# relay.net
KiCad netlist of a schematic drawn in Altium Designer
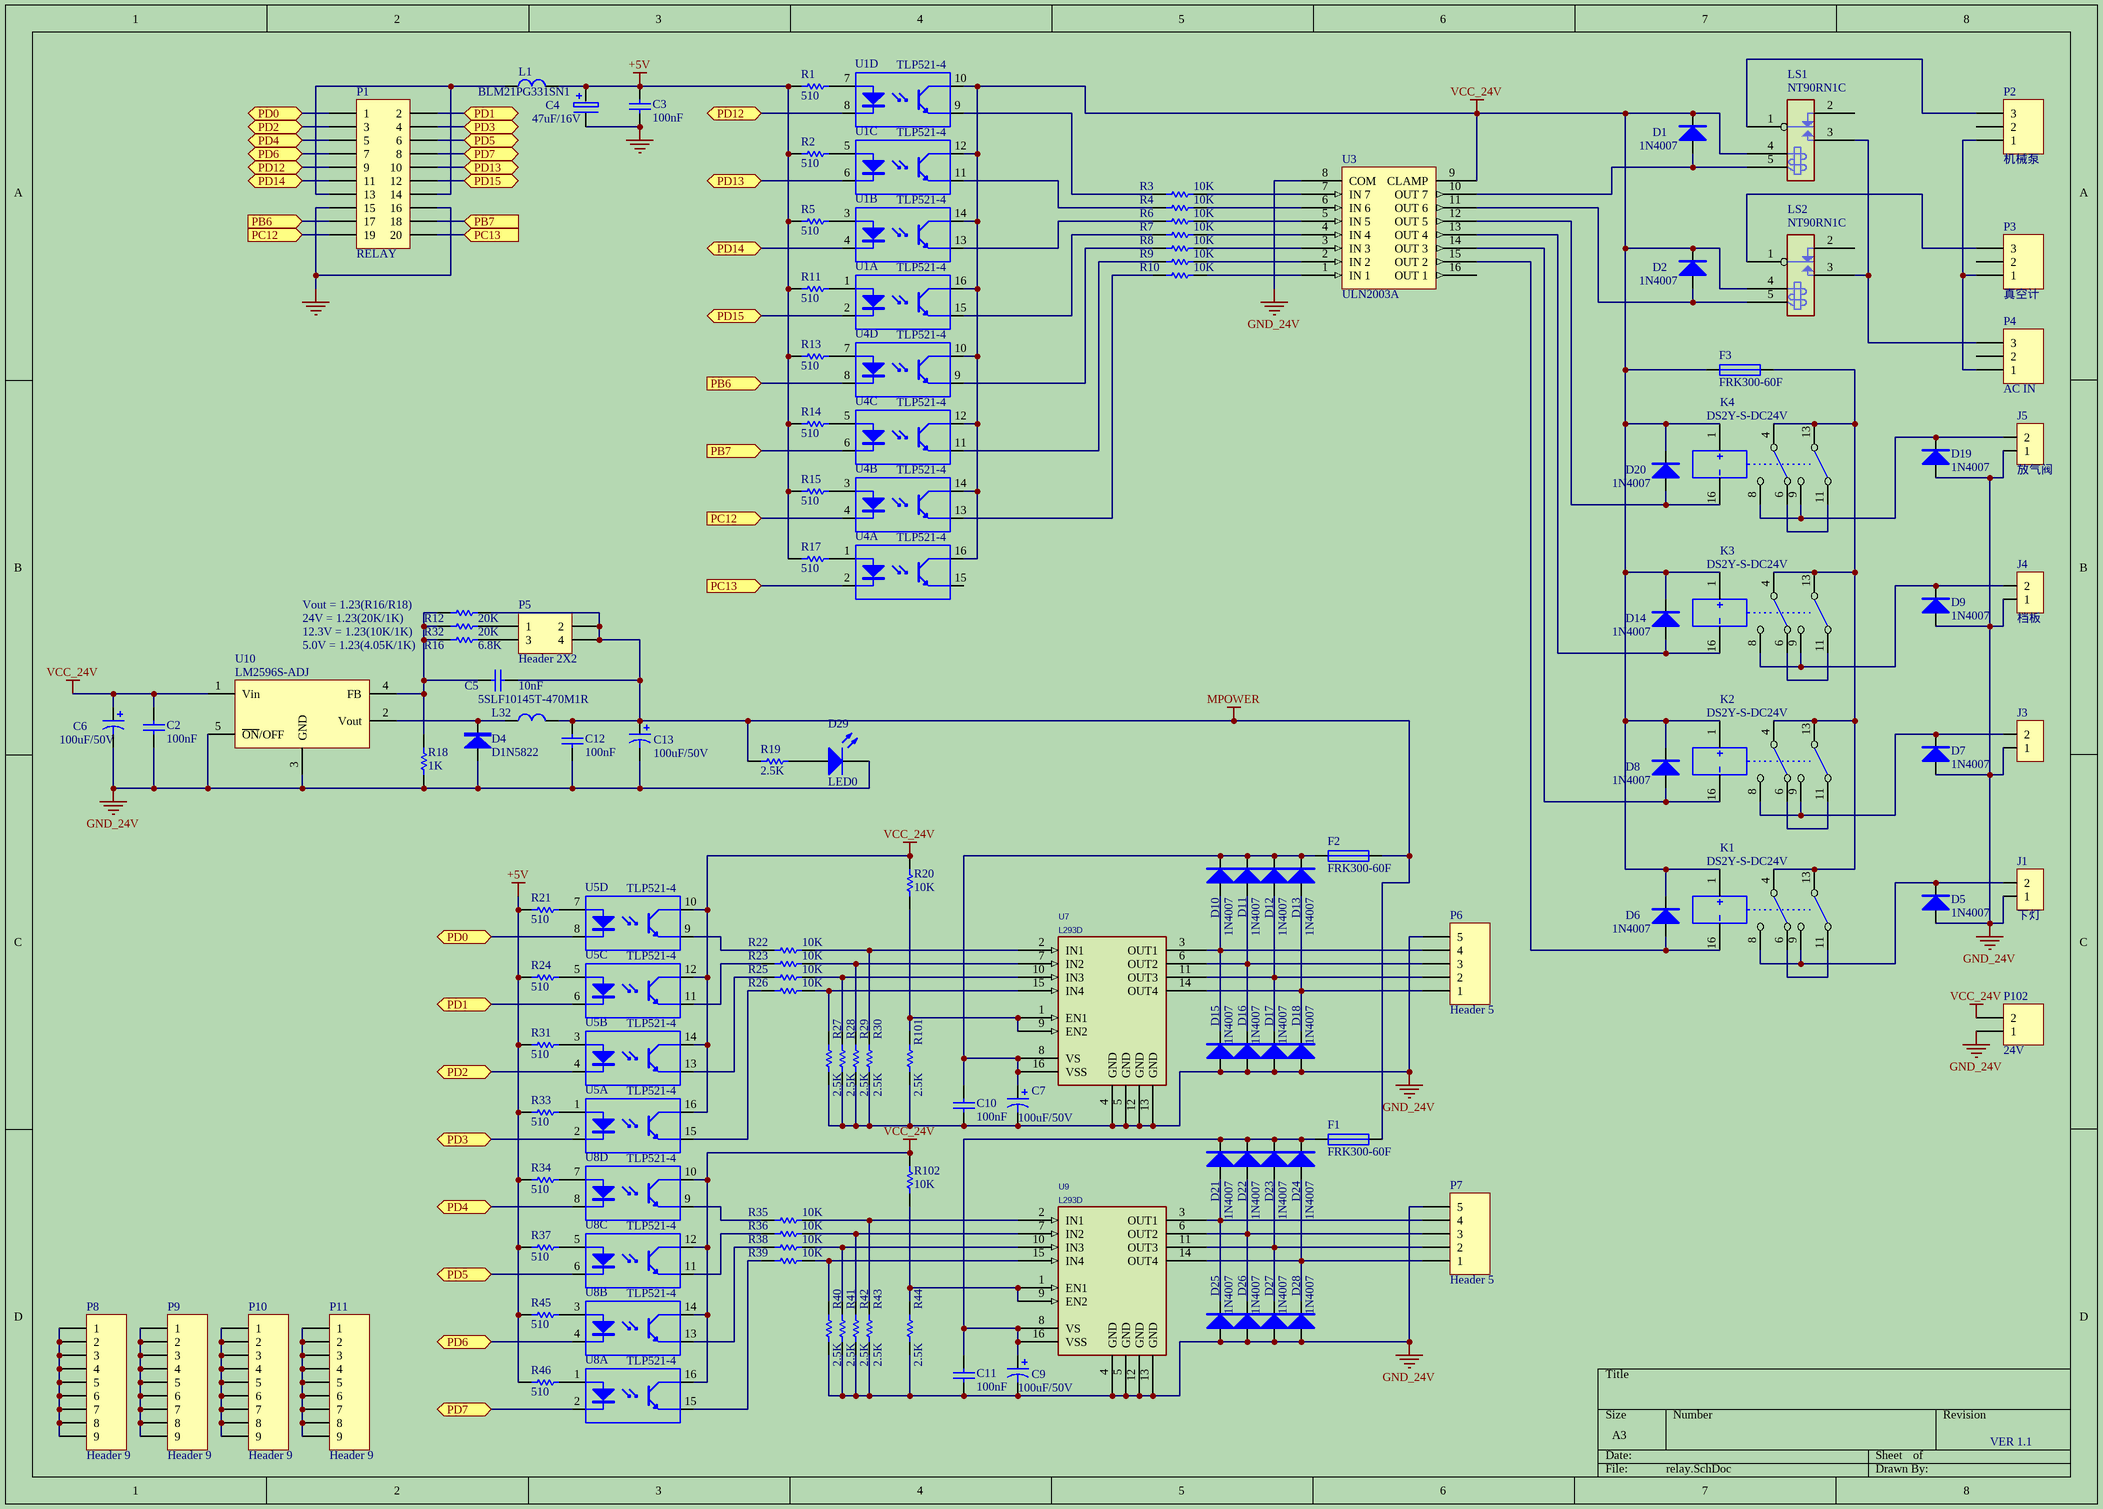
[diagram p0: relay.SchDoc]

(export (version "E")
  (design (tool "Eeschema 10.0.6"))
  (components
    (comp (ref "C2")
      (value "100nF")
      (footprint "C0805")
      (description "Capacitor")
      (fields (field (name "PUBLISHER") "Altium Limited"))
      (libsource (lib "Miscellaneous Devices") (part "Cap"))
    )
    (comp (ref "C3")
      (value "100nF")
      (footprint "贴片元器件:C0805")
      (description "Capacitor")
      (fields (field (name "PUBLISHER") "Altium Limited"))
      (libsource (lib "Miscellaneous Devices") (part "Cap"))
    )
    (comp (ref "C4")
      (value "47uF/16V")
      (footprint "CD1/2")
      (description "Electrolytic Capacitor")
      (libsource (lib "Devices") (part "CD1"))
    )
    (comp (ref "C5")
      (value "10nF")
      (footprint "C0805")
      (description "Capacitor")
      (fields (field (name "PUBLISHER") "Altium Limited"))
      (libsource (lib "Miscellaneous Devices") (part "Cap"))
    )
    (comp (ref "C6")
      (value "100uF/50V")
      (footprint "CD2/4")
      (description "Polarized Capacitor (Radial)")
      (fields (field (name "PUBLISHER") "Altium Limited"))
      (libsource (lib "Miscellaneous Devices") (part "Cap Pol1"))
    )
    (comp (ref "C7")
      (value "100uF/50V")
      (footprint "CD2/4")
      (description "Polarized Capacitor (Radial)")
      (fields (field (name "PUBLISHER") "Altium Limited"))
      (libsource (lib "Miscellaneous Devices") (part "Cap Pol1"))
    )
    (comp (ref "C9")
      (value "100uF/50V")
      (footprint "CD2/4")
      (description "Polarized Capacitor (Radial)")
      (fields (field (name "PUBLISHER") "Altium Limited"))
      (libsource (lib "Miscellaneous Devices") (part "Cap Pol1"))
    )
    (comp (ref "C10")
      (value "100nF")
      (footprint "贴片元器件:C0805")
      (description "Capacitor")
      (fields (field (name "PUBLISHER") "Altium Limited"))
      (libsource (lib "Miscellaneous Devices") (part "Cap"))
    )
    (comp (ref "C11")
      (value "100nF")
      (footprint "贴片元器件:C0805")
      (description "Capacitor")
      (fields (field (name "PUBLISHER") "Altium Limited"))
      (libsource (lib "Miscellaneous Devices") (part "Cap"))
    )
    (comp (ref "C12")
      (value "100nF")
      (footprint "C0805")
      (description "Capacitor")
      (fields (field (name "PUBLISHER") "Altium Limited"))
      (libsource (lib "Miscellaneous Devices") (part "Cap"))
    )
    (comp (ref "C13")
      (value "100uF/50V")
      (footprint "CD2/4")
      (description "Polarized Capacitor (Radial)")
      (fields (field (name "PUBLISHER") "Altium Limited"))
      (libsource (lib "Miscellaneous Devices") (part "Cap Pol1"))
    )
    (comp (ref "D1")
      (value "1N4007")
      (footprint "V3")
      (description "Diode")
      (libsource (lib "Devices") (part "2JG"))
    )
    (comp (ref "D2")
      (value "1N4007")
      (footprint "V3")
      (description "Diode")
      (libsource (lib "Devices") (part "2JG"))
    )
    (comp (ref "D4")
      (value "D1N5822")
      (footprint "DO-201AD-H")
      (description "Diode")
      (libsource (lib "*") (part "DIODE"))
    )
    (comp (ref "D5")
      (value "1N4007")
      (footprint "V3")
      (description "Diode")
      (libsource (lib "Devices") (part "2JG"))
    )
    (comp (ref "D6")
      (value "1N4007")
      (footprint "V3")
      (description "Diode")
      (libsource (lib "Devices") (part "2JG"))
    )
    (comp (ref "D7")
      (value "1N4007")
      (footprint "V3")
      (description "Diode")
      (libsource (lib "Devices") (part "2JG"))
    )
    (comp (ref "D8")
      (value "1N4007")
      (footprint "V3")
      (description "Diode")
      (libsource (lib "Devices") (part "2JG"))
    )
    (comp (ref "D9")
      (value "1N4007")
      (footprint "V3")
      (description "Diode")
      (libsource (lib "Devices") (part "2JG"))
    )
    (comp (ref "D10")
      (value "1N4007")
      (footprint "V3")
      (description "Diode")
      (libsource (lib "Devices") (part "2JG"))
    )
    (comp (ref "D11")
      (value "1N4007")
      (footprint "V3")
      (description "Diode")
      (libsource (lib "Devices") (part "2JG"))
    )
    (comp (ref "D12")
      (value "1N4007")
      (footprint "V3")
      (description "Diode")
      (libsource (lib "Devices") (part "2JG"))
    )
    (comp (ref "D13")
      (value "1N4007")
      (footprint "V3")
      (description "Diode")
      (libsource (lib "Devices") (part "2JG"))
    )
    (comp (ref "D14")
      (value "1N4007")
      (footprint "V3")
      (description "Diode")
      (libsource (lib "Devices") (part "2JG"))
    )
    (comp (ref "D15")
      (value "1N4007")
      (footprint "V3")
      (description "Diode")
      (libsource (lib "Devices") (part "2JG"))
    )
    (comp (ref "D16")
      (value "1N4007")
      (footprint "V3")
      (description "Diode")
      (libsource (lib "Devices") (part "2JG"))
    )
    (comp (ref "D17")
      (value "1N4007")
      (footprint "V3")
      (description "Diode")
      (libsource (lib "Devices") (part "2JG"))
    )
    (comp (ref "D18")
      (value "1N4007")
      (footprint "V3")
      (description "Diode")
      (libsource (lib "Devices") (part "2JG"))
    )
    (comp (ref "D19")
      (value "1N4007")
      (footprint "V3")
      (description "Diode")
      (libsource (lib "Devices") (part "2JG"))
    )
    (comp (ref "D20")
      (value "1N4007")
      (footprint "V3")
      (description "Diode")
      (libsource (lib "Devices") (part "2JG"))
    )
    (comp (ref "D21")
      (value "1N4007")
      (footprint "V3")
      (description "Diode")
      (libsource (lib "Devices") (part "2JG"))
    )
    (comp (ref "D22")
      (value "1N4007")
      (footprint "V3")
      (description "Diode")
      (libsource (lib "Devices") (part "2JG"))
    )
    (comp (ref "D23")
      (value "1N4007")
      (footprint "V3")
      (description "Diode")
      (libsource (lib "Devices") (part "2JG"))
    )
    (comp (ref "D24")
      (value "1N4007")
      (footprint "V3")
      (description "Diode")
      (libsource (lib "Devices") (part "2JG"))
    )
    (comp (ref "D25")
      (value "1N4007")
      (footprint "V3")
      (description "Diode")
      (libsource (lib "Devices") (part "2JG"))
    )
    (comp (ref "D26")
      (value "1N4007")
      (footprint "V3")
      (description "Diode")
      (libsource (lib "Devices") (part "2JG"))
    )
    (comp (ref "D27")
      (value "1N4007")
      (footprint "V3")
      (description "Diode")
      (libsource (lib "Devices") (part "2JG"))
    )
    (comp (ref "D28")
      (value "1N4007")
      (footprint "V3")
      (description "Diode")
      (libsource (lib "Devices") (part "2JG"))
    )
    (comp (ref "D29")
      (value "LED0")
      (footprint "LED0805")
      (description "Typical INFRARED GaAs LED")
      (fields (field (name "PUBLISHER") "Altium Limited"))
      (libsource (lib "Miscellaneous Devices") (part "LED0"))
    )
    (comp (ref "F1")
      (value "FRK300-60F")
      (footprint "RAD-0.2")
      (description "Fuse")
      (libsource (lib "Devices") (part "FUSE1"))
    )
    (comp (ref "F2")
      (value "FRK300-60F")
      (footprint "RAD-0.2")
      (description "Fuse")
      (libsource (lib "Devices") (part "FUSE1"))
    )
    (comp (ref "F3")
      (value "FRK300-60F")
      (footprint "RAD-0.2")
      (description "Fuse")
      (libsource (lib "Devices") (part "FUSE1"))
    )
    (comp (ref "J1")
      (value "下灯")
      (footprint "3.96-2")
      (description "Connector")
      (libsource (lib "Devices") (part "CON2"))
    )
    (comp (ref "J3")
      (value "Valve")
      (footprint "3.96-2")
      (description "Connector")
      (libsource (lib "Devices") (part "CON2"))
    )
    (comp (ref "J4")
      (value "档板")
      (footprint "3.96-2")
      (description "Connector")
      (libsource (lib "Devices") (part "CON2"))
    )
    (comp (ref "J5")
      (value "放气阀")
      (footprint "3.96-2")
      (description "Connector")
      (libsource (lib "Devices") (part "CON2"))
    )
    (comp (ref "K1") (value "DS2Y-S-DC24V") (footprint "DS2Y-S") (libsource (lib "Devices") (part "DS2Y-S")))
    (comp (ref "K2") (value "DS2Y-S-DC24V") (footprint "DS2Y-S") (libsource (lib "Devices") (part "DS2Y-S")))
    (comp (ref "K3") (value "DS2Y-S-DC24V") (footprint "DS2Y-S") (libsource (lib "Devices") (part "DS2Y-S")))
    (comp (ref "K4") (value "DS2Y-S-DC24V") (footprint "DS2Y-S") (libsource (lib "Devices") (part "DS2Y-S")))
    (comp (ref "L1") (value "BLM21PG331SN1") (footprint "L0805") (libsource (lib "Devices") (part "L1")))
    (comp (ref "L32") (value "5SLF10145T-470M1R") (footprint "SLF10145") (libsource (lib "*") (part "L1")))
    (comp (ref "LS1") (value "NT90RN1C") (libsource (lib "Devices") (part "NT90RN1C")))
    (comp (ref "LS2") (value "NT90RN1C") (libsource (lib "Devices") (part "NT90RN1C")))
    (comp (ref "P1")
      (value "RELAY")
      (footprint "IDC20-EJ")
      (description "Header, 10-Pin, Dual row")
      (fields (field (name "PUBLISHER") "Altium Limited"))
      (libsource (lib "Miscellaneous Connectors") (part "Header 10X2"))
    )
    (comp (ref "P2")
      (value "机械泵")
      (footprint "3.96-3")
      (description "Header, 3-Pin, Right Angle")
      (fields (field (name "PUBLISHER") "Altium Limited"))
      (libsource (lib "Miscellaneous Connectors") (part "Header 3H"))
    )
    (comp (ref "P3")
      (value "真空计")
      (footprint "3.96-3")
      (description "Header, 3-Pin, Right Angle")
      (fields (field (name "PUBLISHER") "Altium Limited"))
      (libsource (lib "Miscellaneous Connectors") (part "Header 3H"))
    )
    (comp (ref "P4")
      (value "AC IN")
      (footprint "3.96-3")
      (description "Header, 3-Pin, Right Angle")
      (fields (field (name "PUBLISHER") "Altium Limited"))
      (libsource (lib "Miscellaneous Connectors") (part "Header 3H"))
    )
    (comp (ref "P5")
      (value "Header 2X2")
      (footprint "HDR2X2")
      (description "Header, 2-Pin, Dual row")
      (fields (field (name "PUBLISHER") "Altium Limited"))
      (libsource (lib "Miscellaneous Connectors") (part "Header 2X2"))
    )
    (comp (ref "P6")
      (value "Header 5")
      (footprint "3.96-5")
      (description "Header, 5-Pin")
      (fields (field (name "PUBLISHER") "Altium Limited"))
      (libsource (lib "Miscellaneous Connectors") (part "Header 5"))
    )
    (comp (ref "P7")
      (value "Header 5")
      (footprint "3.96-5")
      (description "Header, 5-Pin")
      (fields (field (name "PUBLISHER") "Altium Limited"))
      (libsource (lib "Miscellaneous Connectors") (part "Header 5"))
    )
    (comp (ref "P8")
      (value "Header 9")
      (footprint "LK")
      (description "Header, 9-Pin")
      (fields (field (name "PUBLISHER") "Altium Limited"))
      (libsource (lib "Miscellaneous Connectors") (part "Header 9"))
    )
    (comp (ref "P9")
      (value "Header 9")
      (footprint "LK")
      (description "Header, 9-Pin")
      (fields (field (name "PUBLISHER") "Altium Limited"))
      (libsource (lib "Miscellaneous Connectors") (part "Header 9"))
    )
    (comp (ref "P10")
      (value "Header 9")
      (footprint "LK")
      (description "Header, 9-Pin")
      (fields (field (name "PUBLISHER") "Altium Limited"))
      (libsource (lib "Miscellaneous Connectors") (part "Header 9"))
    )
    (comp (ref "P11")
      (value "Header 9")
      (footprint "LK")
      (description "Header, 9-Pin")
      (fields (field (name "PUBLISHER") "Altium Limited"))
      (libsource (lib "Miscellaneous Connectors") (part "Header 9"))
    )
    (comp (ref "P102")
      (value "24V")
      (footprint "3.96-2")
      (description "Header, 2-Pin")
      (fields (field (name "PUBLISHER") "Altium Limited"))
      (libsource (lib "Miscellaneous Connectors") (part "Header 2"))
    )
    (comp (ref "R1")
      (value "510")
      (footprint "R0805")
      (description "Resistor")
      (fields (field (name "PUBLISHER") "Altium Limited"))
      (libsource (lib "Miscellaneous Devices") (part "Res1"))
    )
    (comp (ref "R2")
      (value "510")
      (footprint "R0805")
      (description "Resistor")
      (fields (field (name "PUBLISHER") "Altium Limited"))
      (libsource (lib "Miscellaneous Devices") (part "Res1"))
    )
    (comp (ref "R3")
      (value "10K")
      (footprint "R0805")
      (description "Resistor")
      (fields (field (name "PUBLISHER") "Altium Limited"))
      (libsource (lib "Miscellaneous Devices") (part "Res1"))
    )
    (comp (ref "R4")
      (value "10K")
      (footprint "R0805")
      (description "Resistor")
      (fields (field (name "PUBLISHER") "Altium Limited"))
      (libsource (lib "Miscellaneous Devices") (part "Res1"))
    )
    (comp (ref "R5")
      (value "510")
      (footprint "R0805")
      (description "Resistor")
      (fields (field (name "PUBLISHER") "Altium Limited"))
      (libsource (lib "Miscellaneous Devices") (part "Res1"))
    )
    (comp (ref "R6")
      (value "10K")
      (footprint "R0805")
      (description "Resistor")
      (fields (field (name "PUBLISHER") "Altium Limited"))
      (libsource (lib "Miscellaneous Devices") (part "Res1"))
    )
    (comp (ref "R7")
      (value "10K")
      (footprint "R0805")
      (description "Resistor")
      (fields (field (name "PUBLISHER") "Altium Limited"))
      (libsource (lib "Miscellaneous Devices") (part "Res1"))
    )
    (comp (ref "R8")
      (value "10K")
      (footprint "R0805")
      (description "Resistor")
      (fields (field (name "PUBLISHER") "Altium Limited"))
      (libsource (lib "Miscellaneous Devices") (part "Res1"))
    )
    (comp (ref "R9")
      (value "10K")
      (footprint "R0805")
      (description "Resistor")
      (fields (field (name "PUBLISHER") "Altium Limited"))
      (libsource (lib "Miscellaneous Devices") (part "Res1"))
    )
    (comp (ref "R10")
      (value "10K")
      (footprint "R0805")
      (description "Resistor")
      (fields (field (name "PUBLISHER") "Altium Limited"))
      (libsource (lib "Miscellaneous Devices") (part "Res1"))
    )
    (comp (ref "R11")
      (value "510")
      (footprint "R0805")
      (description "Resistor")
      (fields (field (name "PUBLISHER") "Altium Limited"))
      (libsource (lib "Miscellaneous Devices") (part "Res1"))
    )
    (comp (ref "R12")
      (value "20K")
      (footprint "R0805")
      (description "Resistor")
      (fields (field (name "PUBLISHER") "Altium Limited"))
      (libsource (lib "Miscellaneous Devices") (part "Res1"))
    )
    (comp (ref "R13")
      (value "510")
      (footprint "R0805")
      (description "Resistor")
      (fields (field (name "PUBLISHER") "Altium Limited"))
      (libsource (lib "Miscellaneous Devices") (part "Res1"))
    )
    (comp (ref "R14")
      (value "510")
      (footprint "R0805")
      (description "Resistor")
      (fields (field (name "PUBLISHER") "Altium Limited"))
      (libsource (lib "Miscellaneous Devices") (part "Res1"))
    )
    (comp (ref "R15")
      (value "510")
      (footprint "R0805")
      (description "Resistor")
      (fields (field (name "PUBLISHER") "Altium Limited"))
      (libsource (lib "Miscellaneous Devices") (part "Res1"))
    )
    (comp (ref "R16")
      (value "6.8K")
      (footprint "R0805")
      (description "Resistor")
      (fields (field (name "PUBLISHER") "Altium Limited"))
      (libsource (lib "Miscellaneous Devices") (part "Res1"))
    )
    (comp (ref "R17")
      (value "510")
      (footprint "R0805")
      (description "Resistor")
      (fields (field (name "PUBLISHER") "Altium Limited"))
      (libsource (lib "Miscellaneous Devices") (part "Res1"))
    )
    (comp (ref "R18")
      (value "1K")
      (footprint "R0805")
      (description "Resistor")
      (fields (field (name "PUBLISHER") "Altium Limited"))
      (libsource (lib "Miscellaneous Devices") (part "Res1"))
    )
    (comp (ref "R19")
      (value "2.5K")
      (footprint "R0805")
      (description "Resistor")
      (fields (field (name "PUBLISHER") "Altium Limited"))
      (libsource (lib "Miscellaneous Devices") (part "Res1"))
    )
    (comp (ref "R20")
      (value "10K")
      (footprint "R0805")
      (description "Resistor")
      (fields (field (name "PUBLISHER") "Altium Limited"))
      (libsource (lib "Miscellaneous Devices") (part "Res1"))
    )
    (comp (ref "R21")
      (value "510")
      (footprint "R0805")
      (description "Resistor")
      (fields (field (name "PUBLISHER") "Altium Limited"))
      (libsource (lib "Miscellaneous Devices") (part "Res1"))
    )
    (comp (ref "R22")
      (value "10K")
      (footprint "R0805")
      (description "Resistor")
      (fields (field (name "PUBLISHER") "Altium Limited"))
      (libsource (lib "Miscellaneous Devices") (part "Res1"))
    )
    (comp (ref "R23")
      (value "10K")
      (footprint "R0805")
      (description "Resistor")
      (fields (field (name "PUBLISHER") "Altium Limited"))
      (libsource (lib "Miscellaneous Devices") (part "Res1"))
    )
    (comp (ref "R24")
      (value "510")
      (footprint "R0805")
      (description "Resistor")
      (fields (field (name "PUBLISHER") "Altium Limited"))
      (libsource (lib "Miscellaneous Devices") (part "Res1"))
    )
    (comp (ref "R25")
      (value "10K")
      (footprint "R0805")
      (description "Resistor")
      (fields (field (name "PUBLISHER") "Altium Limited"))
      (libsource (lib "Miscellaneous Devices") (part "Res1"))
    )
    (comp (ref "R26")
      (value "10K")
      (footprint "R0805")
      (description "Resistor")
      (fields (field (name "PUBLISHER") "Altium Limited"))
      (libsource (lib "Miscellaneous Devices") (part "Res1"))
    )
    (comp (ref "R27")
      (value "2.5K")
      (footprint "R0805")
      (description "Resistor")
      (fields (field (name "PUBLISHER") "Altium Limited"))
      (libsource (lib "Miscellaneous Devices") (part "Res1"))
    )
    (comp (ref "R28")
      (value "2.5K")
      (footprint "R0805")
      (description "Resistor")
      (fields (field (name "PUBLISHER") "Altium Limited"))
      (libsource (lib "Miscellaneous Devices") (part "Res1"))
    )
    (comp (ref "R29")
      (value "2.5K")
      (footprint "R0805")
      (description "Resistor")
      (fields (field (name "PUBLISHER") "Altium Limited"))
      (libsource (lib "Miscellaneous Devices") (part "Res1"))
    )
    (comp (ref "R30")
      (value "2.5K")
      (footprint "R0805")
      (description "Resistor")
      (fields (field (name "PUBLISHER") "Altium Limited"))
      (libsource (lib "Miscellaneous Devices") (part "Res1"))
    )
    (comp (ref "R31")
      (value "510")
      (footprint "R0805")
      (description "Resistor")
      (fields (field (name "PUBLISHER") "Altium Limited"))
      (libsource (lib "Miscellaneous Devices") (part "Res1"))
    )
    (comp (ref "R32")
      (value "20K")
      (footprint "R0805")
      (description "Resistor")
      (fields (field (name "PUBLISHER") "Altium Limited"))
      (libsource (lib "Miscellaneous Devices") (part "Res1"))
    )
    (comp (ref "R33")
      (value "510")
      (footprint "R0805")
      (description "Resistor")
      (fields (field (name "PUBLISHER") "Altium Limited"))
      (libsource (lib "Miscellaneous Devices") (part "Res1"))
    )
    (comp (ref "R34")
      (value "510")
      (footprint "R0805")
      (description "Resistor")
      (fields (field (name "PUBLISHER") "Altium Limited"))
      (libsource (lib "Miscellaneous Devices") (part "Res1"))
    )
    (comp (ref "R35")
      (value "10K")
      (footprint "R0805")
      (description "Resistor")
      (fields (field (name "PUBLISHER") "Altium Limited"))
      (libsource (lib "Miscellaneous Devices") (part "Res1"))
    )
    (comp (ref "R36")
      (value "10K")
      (footprint "R0805")
      (description "Resistor")
      (fields (field (name "PUBLISHER") "Altium Limited"))
      (libsource (lib "Miscellaneous Devices") (part "Res1"))
    )
    (comp (ref "R37")
      (value "510")
      (footprint "R0805")
      (description "Resistor")
      (fields (field (name "PUBLISHER") "Altium Limited"))
      (libsource (lib "Miscellaneous Devices") (part "Res1"))
    )
    (comp (ref "R38")
      (value "10K")
      (footprint "R0805")
      (description "Resistor")
      (fields (field (name "PUBLISHER") "Altium Limited"))
      (libsource (lib "Miscellaneous Devices") (part "Res1"))
    )
    (comp (ref "R39")
      (value "10K")
      (footprint "R0805")
      (description "Resistor")
      (fields (field (name "PUBLISHER") "Altium Limited"))
      (libsource (lib "Miscellaneous Devices") (part "Res1"))
    )
    (comp (ref "R40")
      (value "2.5K")
      (footprint "R0805")
      (description "Resistor")
      (fields (field (name "PUBLISHER") "Altium Limited"))
      (libsource (lib "Miscellaneous Devices") (part "Res1"))
    )
    (comp (ref "R41")
      (value "2.5K")
      (footprint "R0805")
      (description "Resistor")
      (fields (field (name "PUBLISHER") "Altium Limited"))
      (libsource (lib "Miscellaneous Devices") (part "Res1"))
    )
    (comp (ref "R42")
      (value "2.5K")
      (footprint "R0805")
      (description "Resistor")
      (fields (field (name "PUBLISHER") "Altium Limited"))
      (libsource (lib "Miscellaneous Devices") (part "Res1"))
    )
    (comp (ref "R43")
      (value "2.5K")
      (footprint "R0805")
      (description "Resistor")
      (fields (field (name "PUBLISHER") "Altium Limited"))
      (libsource (lib "Miscellaneous Devices") (part "Res1"))
    )
    (comp (ref "R44")
      (value "2.5K")
      (footprint "R0805")
      (description "Resistor")
      (fields (field (name "PUBLISHER") "Altium Limited"))
      (libsource (lib "Miscellaneous Devices") (part "Res1"))
    )
    (comp (ref "R45")
      (value "510")
      (footprint "R0805")
      (description "Resistor")
      (fields (field (name "PUBLISHER") "Altium Limited"))
      (libsource (lib "Miscellaneous Devices") (part "Res1"))
    )
    (comp (ref "R46")
      (value "510")
      (footprint "R0805")
      (description "Resistor")
      (fields (field (name "PUBLISHER") "Altium Limited"))
      (libsource (lib "Miscellaneous Devices") (part "Res1"))
    )
    (comp (ref "R101")
      (value "2.5K")
      (footprint "R0805")
      (description "Resistor")
      (fields (field (name "PUBLISHER") "Altium Limited"))
      (libsource (lib "Miscellaneous Devices") (part "Res1"))
    )
    (comp (ref "R102")
      (value "10K")
      (footprint "R0805")
      (description "Resistor")
      (fields (field (name "PUBLISHER") "Altium Limited"))
      (libsource (lib "Miscellaneous Devices") (part "Res1"))
    )
    (comp (ref "U1") (value "TLP521-4") (footprint "DIP16") (libsource (lib "IC") (part "TLP521-4")))
    (comp (ref "U3")
      (value "ULN2003A")
      (footprint "so16")
      (description "HIGH-VOLTAGE,HIGH-CURRENT DARLINGTON ARRAYS")
      (libsource (lib "IC") (part "ULN2003A"))
    )
    (comp (ref "U4") (value "TLP521-4") (footprint "DIP16") (libsource (lib "IC") (part "TLP521-4")))
    (comp (ref "U5") (value "TLP521-4") (footprint "DIP16") (libsource (lib "IC") (part "TLP521-4")))
    (comp (ref "U7") (value "L293D") (libsource (lib "*") (part "L293D_0")))
    (comp (ref "U8") (value "TLP521-4") (footprint "DIP16") (libsource (lib "IC") (part "TLP521-4")))
    (comp (ref "U9") (value "L293D") (libsource (lib "*") (part "L293D_0")))
    (comp (ref "U10")
      (value "LM2596S-ADJ")
      (footprint "TO263-5")
      (description "SIMPLESWITCHER PowerConverter150kHz 3A Step-DownVoltageRegulator")
      (libsource (lib "*") (part "LM2596"))
    )
  )
  (nets
    (net (code "1") (name "+5V") (class "Default")
      (node (ref "C3") (pin "2") (pinfunction "2_2") (pintype "passive"))
      (node (ref "C4") (pin "1") (pinfunction "1_1") (pintype "passive"))
      (node (ref "L1") (pin "2") (pinfunction "2_2") (pintype "passive"))
      (node (ref "R1") (pin "2") (pinfunction "2_2") (pintype "passive"))
      (node (ref "R11") (pin "2") (pinfunction "2_2") (pintype "passive"))
      (node (ref "R13") (pin "2") (pinfunction "2_2") (pintype "passive"))
      (node (ref "R14") (pin "2") (pinfunction "2_2") (pintype "passive"))
      (node (ref "R15") (pin "2") (pinfunction "2_2") (pintype "passive"))
      (node (ref "R17") (pin "2") (pinfunction "2_2") (pintype "passive"))
      (node (ref "R2") (pin "2") (pinfunction "2_2") (pintype "passive"))
      (node (ref "R21") (pin "2") (pinfunction "2_2") (pintype "passive"))
      (node (ref "R24") (pin "2") (pinfunction "2_2") (pintype "passive"))
      (node (ref "R31") (pin "2") (pinfunction "2_2") (pintype "passive"))
      (node (ref "R33") (pin "2") (pinfunction "2_2") (pintype "passive"))
      (node (ref "R34") (pin "2") (pinfunction "2_2") (pintype "passive"))
      (node (ref "R37") (pin "2") (pinfunction "2_2") (pintype "passive"))
      (node (ref "R45") (pin "2") (pinfunction "2_2") (pintype "passive"))
      (node (ref "R46") (pin "2") (pinfunction "2_2") (pintype "passive"))
      (node (ref "R5") (pin "2") (pinfunction "2_2") (pintype "passive"))
    )
    (net (code "2") (name "/PB6") (class "Default")
      (node (ref "P1") (pin "17") (pinfunction "17_17") (pintype "passive"))
      (node (ref "U4") (pin "8") (pinfunction "K_8") (pintype "passive"))
    )
    (net (code "3") (name "/PB7") (class "Default")
      (node (ref "P1") (pin "18") (pinfunction "18_18") (pintype "passive"))
      (node (ref "U4") (pin "6") (pinfunction "K_6") (pintype "passive"))
    )
    (net (code "4") (name "/PC12") (class "Default")
      (node (ref "P1") (pin "19") (pinfunction "19_19") (pintype "passive"))
      (node (ref "U4") (pin "4") (pinfunction "K_4") (pintype "passive"))
    )
    (net (code "5") (name "/PC13") (class "Default")
      (node (ref "P1") (pin "20") (pinfunction "20_20") (pintype "passive"))
      (node (ref "U4") (pin "2") (pinfunction "K_2") (pintype "passive"))
    )
    (net (code "6") (name "/PD0") (class "Default")
      (node (ref "P1") (pin "1") (pinfunction "1_1") (pintype "passive"))
      (node (ref "U5") (pin "8") (pinfunction "K_8") (pintype "passive"))
    )
    (net (code "7") (name "/PD1") (class "Default")
      (node (ref "P1") (pin "2") (pinfunction "2_2") (pintype "passive"))
      (node (ref "U5") (pin "6") (pinfunction "K_6") (pintype "passive"))
    )
    (net (code "8") (name "/PD2") (class "Default")
      (node (ref "P1") (pin "3") (pinfunction "3_3") (pintype "passive"))
      (node (ref "U5") (pin "4") (pinfunction "K_4") (pintype "passive"))
    )
    (net (code "9") (name "/PD3") (class "Default")
      (node (ref "P1") (pin "4") (pinfunction "4_4") (pintype "passive"))
      (node (ref "U5") (pin "2") (pinfunction "K_2") (pintype "passive"))
    )
    (net (code "10") (name "/PD4") (class "Default")
      (node (ref "P1") (pin "5") (pinfunction "5_5") (pintype "passive"))
      (node (ref "U8") (pin "8") (pinfunction "K_8") (pintype "passive"))
    )
    (net (code "11") (name "/PD5") (class "Default")
      (node (ref "P1") (pin "6") (pinfunction "6_6") (pintype "passive"))
      (node (ref "U8") (pin "6") (pinfunction "K_6") (pintype "passive"))
    )
    (net (code "12") (name "/PD6") (class "Default")
      (node (ref "P1") (pin "7") (pinfunction "7_7") (pintype "passive"))
      (node (ref "U8") (pin "4") (pinfunction "K_4") (pintype "passive"))
    )
    (net (code "13") (name "/PD7") (class "Default")
      (node (ref "P1") (pin "8") (pinfunction "8_8") (pintype "passive"))
      (node (ref "U8") (pin "2") (pinfunction "K_2") (pintype "passive"))
    )
    (net (code "14") (name "/PD12") (class "Default")
      (node (ref "P1") (pin "9") (pinfunction "9_9") (pintype "passive"))
      (node (ref "U1") (pin "8") (pinfunction "K_8") (pintype "passive"))
    )
    (net (code "15") (name "/PD13") (class "Default")
      (node (ref "P1") (pin "10") (pinfunction "10_10") (pintype "passive"))
      (node (ref "U1") (pin "6") (pinfunction "K_6") (pintype "passive"))
    )
    (net (code "16") (name "/PD14") (class "Default")
      (node (ref "P1") (pin "11") (pinfunction "11_11") (pintype "passive"))
      (node (ref "U1") (pin "4") (pinfunction "K_4") (pintype "passive"))
    )
    (net (code "17") (name "/PD15") (class "Default")
      (node (ref "P1") (pin "12") (pinfunction "12_12") (pintype "passive"))
      (node (ref "U1") (pin "2") (pinfunction "K_2") (pintype "passive"))
    )
    (net (code "18") (name "GND") (class "Default")
      (node (ref "C3") (pin "1") (pinfunction "1_1") (pintype "passive"))
      (node (ref "C4") (pin "2") (pinfunction "2_2") (pintype "passive"))
      (node (ref "P1") (pin "15") (pinfunction "15_15") (pintype "passive"))
      (node (ref "P1") (pin "16") (pinfunction "16_16") (pintype "passive"))
    )
    (net (code "19") (name "GND_24V") (class "Default")
      (node (ref "C10") (pin "1") (pinfunction "1_1") (pintype "passive"))
      (node (ref "C11") (pin "1") (pinfunction "1_1") (pintype "passive"))
      (node (ref "C12") (pin "1") (pinfunction "1_1") (pintype "passive"))
      (node (ref "C13") (pin "2") (pinfunction "2_2") (pintype "passive"))
      (node (ref "C2") (pin "1") (pinfunction "1_1") (pintype "passive"))
      (node (ref "C6") (pin "2") (pinfunction "2_2") (pintype "passive"))
      (node (ref "C7") (pin "2") (pinfunction "2_2") (pintype "passive"))
      (node (ref "C9") (pin "2") (pinfunction "2_2") (pintype "passive"))
      (node (ref "D15") (pin "1") (pinfunction "A_1") (pintype "passive"))
      (node (ref "D16") (pin "1") (pinfunction "A_1") (pintype "passive"))
      (node (ref "D17") (pin "1") (pinfunction "A_1") (pintype "passive"))
      (node (ref "D18") (pin "1") (pinfunction "A_1") (pintype "passive"))
      (node (ref "D19") (pin "1") (pinfunction "A_1") (pintype "passive"))
      (node (ref "D25") (pin "1") (pinfunction "A_1") (pintype "passive"))
      (node (ref "D26") (pin "1") (pinfunction "A_1") (pintype "passive"))
      (node (ref "D27") (pin "1") (pinfunction "A_1") (pintype "passive"))
      (node (ref "D28") (pin "1") (pinfunction "A_1") (pintype "passive"))
      (node (ref "D29") (pin "2") (pinfunction "K_2") (pintype "passive"))
      (node (ref "D4") (pin "1") (pinfunction "1_1") (pintype "passive"))
      (node (ref "D5") (pin "1") (pinfunction "A_1") (pintype "passive"))
      (node (ref "D7") (pin "1") (pinfunction "A_1") (pintype "passive"))
      (node (ref "D9") (pin "1") (pinfunction "A_1") (pintype "passive"))
      (node (ref "J1") (pin "1") (pinfunction "1_1") (pintype "passive"))
      (node (ref "J3") (pin "1") (pinfunction "1_1") (pintype "passive"))
      (node (ref "J4") (pin "1") (pinfunction "1_1") (pintype "passive"))
      (node (ref "J5") (pin "1") (pinfunction "1_1") (pintype "passive"))
      (node (ref "P102") (pin "1") (pinfunction "1_1") (pintype "passive"))
      (node (ref "P6") (pin "5") (pinfunction "5_5") (pintype "passive"))
      (node (ref "P7") (pin "5") (pinfunction "5_5") (pintype "passive"))
      (node (ref "R101") (pin "1") (pinfunction "1_1") (pintype "passive"))
      (node (ref "R18") (pin "2") (pinfunction "2_2") (pintype "passive"))
      (node (ref "R27") (pin "1") (pinfunction "1_1") (pintype "passive"))
      (node (ref "R28") (pin "1") (pinfunction "1_1") (pintype "passive"))
      (node (ref "R29") (pin "1") (pinfunction "1_1") (pintype "passive"))
      (node (ref "R30") (pin "1") (pinfunction "1_1") (pintype "passive"))
      (node (ref "R40") (pin "1") (pinfunction "1_1") (pintype "passive"))
      (node (ref "R41") (pin "1") (pinfunction "1_1") (pintype "passive"))
      (node (ref "R42") (pin "1") (pinfunction "1_1") (pintype "passive"))
      (node (ref "R43") (pin "1") (pinfunction "1_1") (pintype "passive"))
      (node (ref "R44") (pin "1") (pinfunction "1_1") (pintype "passive"))
      (node (ref "U10") (pin "3") (pinfunction "GND_3") (pintype "passive"))
      (node (ref "U10") (pin "5") (pinfunction "~{ON}/OFF_5") (pintype "passive"))
      (node (ref "U3") (pin "8") (pinfunction "COM_8") (pintype "passive"))
      (node (ref "U7") (pin "12") (pinfunction "GND_12") (pintype "power_in"))
      (node (ref "U7") (pin "13") (pinfunction "GND_13") (pintype "power_in"))
      (node (ref "U7") (pin "4") (pinfunction "GND_4") (pintype "power_in"))
      (node (ref "U7") (pin "5") (pinfunction "GND_5") (pintype "power_in"))
      (node (ref "U9") (pin "12") (pinfunction "GND_12") (pintype "power_in"))
      (node (ref "U9") (pin "13") (pinfunction "GND_13") (pintype "power_in"))
      (node (ref "U9") (pin "4") (pinfunction "GND_4") (pintype "power_in"))
      (node (ref "U9") (pin "5") (pinfunction "GND_5") (pintype "power_in"))
    )
    (net (code "20") (name "MPOWER") (class "Default")
      (node (ref "C12") (pin "2") (pinfunction "2_2") (pintype "passive"))
      (node (ref "C13") (pin "1") (pinfunction "1_1") (pintype "passive"))
      (node (ref "C5") (pin "1") (pinfunction "1_1") (pintype "passive"))
      (node (ref "F1") (pin "2") (pinfunction "2_2") (pintype "passive"))
      (node (ref "F2") (pin "2") (pinfunction "2_2") (pintype "passive"))
      (node (ref "L32") (pin "2") (pinfunction "2_2") (pintype "passive"))
      (node (ref "P5") (pin "2") (pinfunction "2_2") (pintype "passive"))
      (node (ref "P5") (pin "4") (pinfunction "4_4") (pintype "passive"))
      (node (ref "R12") (pin "2") (pinfunction "2_2") (pintype "passive"))
      (node (ref "R19") (pin "2") (pinfunction "2_2") (pintype "passive"))
    )
    (net (code "21") (name "Net-(D1-A)") (class "Default")
      (node (ref "D1") (pin "1") (pinfunction "A_1") (pintype "passive"))
      (node (ref "LS1") (pin "5") (pinfunction "COIL2_5") (pintype "passive"))
      (node (ref "U3") (pin "10") (pinfunction "OUT_7_10") (pintype "output"))
    )
    (net (code "22") (name "Net-(D2-A)") (class "Default")
      (node (ref "D2") (pin "1") (pinfunction "A_1") (pintype "passive"))
      (node (ref "LS2") (pin "5") (pinfunction "COIL2_5") (pintype "passive"))
      (node (ref "U3") (pin "11") (pinfunction "OUT_6_11") (pintype "output"))
    )
    (net (code "23") (name "Net-(D5-K)") (class "Default")
      (node (ref "D5") (pin "2") (pinfunction "K_2") (pintype "passive"))
      (node (ref "J1") (pin "2") (pinfunction "2_2") (pintype "passive"))
      (node (ref "K1") (pin "8") (pinfunction "N.O._8") (pintype "passive"))
      (node (ref "K1") (pin "9") (pinfunction "N.O._9") (pintype "passive"))
    )
    (net (code "24") (name "Net-(D6-A)") (class "Default")
      (node (ref "D6") (pin "1") (pinfunction "A_1") (pintype "passive"))
      (node (ref "K1") (pin "16") (pinfunction "-_16") (pintype "passive"))
      (node (ref "U3") (pin "15") (pinfunction "OUT_2_15") (pintype "output"))
    )
    (net (code "25") (name "Net-(D7-K)") (class "Default")
      (node (ref "D7") (pin "2") (pinfunction "K_2") (pintype "passive"))
      (node (ref "J3") (pin "2") (pinfunction "2_2") (pintype "passive"))
      (node (ref "K2") (pin "8") (pinfunction "N.O._8") (pintype "passive"))
      (node (ref "K2") (pin "9") (pinfunction "N.O._9") (pintype "passive"))
    )
    (net (code "26") (name "Net-(D8-A)") (class "Default")
      (node (ref "D8") (pin "1") (pinfunction "A_1") (pintype "passive"))
      (node (ref "K2") (pin "16") (pinfunction "-_16") (pintype "passive"))
      (node (ref "U3") (pin "14") (pinfunction "OUT_3_14") (pintype "output"))
    )
    (net (code "27") (name "Net-(D9-K)") (class "Default")
      (node (ref "D9") (pin "2") (pinfunction "K_2") (pintype "passive"))
      (node (ref "J4") (pin "2") (pinfunction "2_2") (pintype "passive"))
      (node (ref "K3") (pin "8") (pinfunction "N.O._8") (pintype "passive"))
      (node (ref "K3") (pin "9") (pinfunction "N.O._9") (pintype "passive"))
    )
    (net (code "28") (name "Net-(D10-A)") (class "Default")
      (node (ref "D10") (pin "1") (pinfunction "A_1") (pintype "passive"))
      (node (ref "D15") (pin "2") (pinfunction "K_2") (pintype "passive"))
      (node (ref "P6") (pin "4") (pinfunction "4_4") (pintype "passive"))
      (node (ref "U7") (pin "3") (pinfunction "OUT1_3") (pintype "tri_state"))
    )
    (net (code "29") (name "Net-(D10-K)") (class "Default")
      (node (ref "C10") (pin "2") (pinfunction "2_2") (pintype "passive"))
      (node (ref "C7") (pin "1") (pinfunction "1_1") (pintype "passive"))
      (node (ref "D10") (pin "2") (pinfunction "K_2") (pintype "passive"))
      (node (ref "D11") (pin "2") (pinfunction "K_2") (pintype "passive"))
      (node (ref "D12") (pin "2") (pinfunction "K_2") (pintype "passive"))
      (node (ref "D13") (pin "2") (pinfunction "K_2") (pintype "passive"))
      (node (ref "F2") (pin "1") (pinfunction "1_1") (pintype "passive"))
      (node (ref "U7") (pin "16") (pinfunction "VSS_16") (pintype "power_in"))
      (node (ref "U7") (pin "8") (pinfunction "VS_8") (pintype "power_in"))
    )
    (net (code "30") (name "Net-(D11-A)") (class "Default")
      (node (ref "D11") (pin "1") (pinfunction "A_1") (pintype "passive"))
      (node (ref "D16") (pin "2") (pinfunction "K_2") (pintype "passive"))
      (node (ref "P6") (pin "3") (pinfunction "3_3") (pintype "passive"))
      (node (ref "U7") (pin "6") (pinfunction "OUT2_6") (pintype "tri_state"))
    )
    (net (code "31") (name "Net-(D12-A)") (class "Default")
      (node (ref "D12") (pin "1") (pinfunction "A_1") (pintype "passive"))
      (node (ref "D17") (pin "2") (pinfunction "K_2") (pintype "passive"))
      (node (ref "P6") (pin "2") (pinfunction "2_2") (pintype "passive"))
      (node (ref "U7") (pin "11") (pinfunction "OUT3_11") (pintype "tri_state"))
    )
    (net (code "32") (name "Net-(D13-A)") (class "Default")
      (node (ref "D13") (pin "1") (pinfunction "A_1") (pintype "passive"))
      (node (ref "D18") (pin "2") (pinfunction "K_2") (pintype "passive"))
      (node (ref "P6") (pin "1") (pinfunction "1_1") (pintype "passive"))
      (node (ref "U7") (pin "14") (pinfunction "OUT4_14") (pintype "tri_state"))
    )
    (net (code "33") (name "Net-(D14-A)") (class "Default")
      (node (ref "D14") (pin "1") (pinfunction "A_1") (pintype "passive"))
      (node (ref "K3") (pin "16") (pinfunction "-_16") (pintype "passive"))
      (node (ref "U3") (pin "13") (pinfunction "OUT_4_13") (pintype "output"))
    )
    (net (code "34") (name "Net-(D19-K)") (class "Default")
      (node (ref "D19") (pin "2") (pinfunction "K_2") (pintype "passive"))
      (node (ref "J5") (pin "2") (pinfunction "2_2") (pintype "passive"))
      (node (ref "K4") (pin "8") (pinfunction "N.O._8") (pintype "passive"))
      (node (ref "K4") (pin "9") (pinfunction "N.O._9") (pintype "passive"))
    )
    (net (code "35") (name "Net-(D20-A)") (class "Default")
      (node (ref "D20") (pin "1") (pinfunction "A_1") (pintype "passive"))
      (node (ref "K4") (pin "16") (pinfunction "-_16") (pintype "passive"))
      (node (ref "U3") (pin "12") (pinfunction "OUT_5_12") (pintype "output"))
    )
    (net (code "36") (name "Net-(D21-A)") (class "Default")
      (node (ref "D21") (pin "1") (pinfunction "A_1") (pintype "passive"))
      (node (ref "D25") (pin "2") (pinfunction "K_2") (pintype "passive"))
      (node (ref "P7") (pin "4") (pinfunction "4_4") (pintype "passive"))
      (node (ref "U9") (pin "3") (pinfunction "OUT1_3") (pintype "tri_state"))
    )
    (net (code "37") (name "Net-(D21-K)") (class "Default")
      (node (ref "C11") (pin "2") (pinfunction "2_2") (pintype "passive"))
      (node (ref "C9") (pin "1") (pinfunction "1_1") (pintype "passive"))
      (node (ref "D21") (pin "2") (pinfunction "K_2") (pintype "passive"))
      (node (ref "D22") (pin "2") (pinfunction "K_2") (pintype "passive"))
      (node (ref "D23") (pin "2") (pinfunction "K_2") (pintype "passive"))
      (node (ref "D24") (pin "2") (pinfunction "K_2") (pintype "passive"))
      (node (ref "F1") (pin "1") (pinfunction "1_1") (pintype "passive"))
      (node (ref "U9") (pin "16") (pinfunction "VSS_16") (pintype "power_in"))
      (node (ref "U9") (pin "8") (pinfunction "VS_8") (pintype "power_in"))
    )
    (net (code "38") (name "Net-(D22-A)") (class "Default")
      (node (ref "D22") (pin "1") (pinfunction "A_1") (pintype "passive"))
      (node (ref "D26") (pin "2") (pinfunction "K_2") (pintype "passive"))
      (node (ref "P7") (pin "3") (pinfunction "3_3") (pintype "passive"))
      (node (ref "U9") (pin "6") (pinfunction "OUT2_6") (pintype "tri_state"))
    )
    (net (code "39") (name "Net-(D23-A)") (class "Default")
      (node (ref "D23") (pin "1") (pinfunction "A_1") (pintype "passive"))
      (node (ref "D27") (pin "2") (pinfunction "K_2") (pintype "passive"))
      (node (ref "P7") (pin "2") (pinfunction "2_2") (pintype "passive"))
      (node (ref "U9") (pin "11") (pinfunction "OUT3_11") (pintype "tri_state"))
    )
    (net (code "40") (name "Net-(D24-A)") (class "Default")
      (node (ref "D24") (pin "1") (pinfunction "A_1") (pintype "passive"))
      (node (ref "D28") (pin "2") (pinfunction "K_2") (pintype "passive"))
      (node (ref "P7") (pin "1") (pinfunction "1_1") (pintype "passive"))
      (node (ref "U9") (pin "14") (pinfunction "OUT4_14") (pintype "tri_state"))
    )
    (net (code "41") (name "Net-(D29-A)") (class "Default")
      (node (ref "D29") (pin "1") (pinfunction "A_1") (pintype "passive"))
      (node (ref "R19") (pin "1") (pinfunction "1_1") (pintype "passive"))
    )
    (net (code "42") (name "Net-(F3-Pad2)") (class "Default")
      (node (ref "F3") (pin "2") (pinfunction "2_2") (pintype "passive"))
      (node (ref "K1") (pin "13") (pinfunction "COM_13") (pintype "passive"))
      (node (ref "K1") (pin "4") (pinfunction "COM_4") (pintype "passive"))
      (node (ref "K2") (pin "13") (pinfunction "COM_13") (pintype "passive"))
      (node (ref "K2") (pin "4") (pinfunction "COM_4") (pintype "passive"))
      (node (ref "K3") (pin "13") (pinfunction "COM_13") (pintype "passive"))
      (node (ref "K3") (pin "4") (pinfunction "COM_4") (pintype "passive"))
      (node (ref "K4") (pin "13") (pinfunction "COM_13") (pintype "passive"))
      (node (ref "K4") (pin "4") (pinfunction "COM_4") (pintype "passive"))
    )
    (net (code "43") (name "Net-(K1-N.C.-Pad11)") (class "Default")
      (node (ref "K1") (pin "11") (pinfunction "N.C._11") (pintype "passive"))
      (node (ref "K1") (pin "6") (pinfunction "N.C._6") (pintype "passive"))
    )
    (net (code "44") (name "Net-(K2-N.C.-Pad11)") (class "Default")
      (node (ref "K2") (pin "11") (pinfunction "N.C._11") (pintype "passive"))
      (node (ref "K2") (pin "6") (pinfunction "N.C._6") (pintype "passive"))
    )
    (net (code "45") (name "Net-(K3-N.C.-Pad11)") (class "Default")
      (node (ref "K3") (pin "11") (pinfunction "N.C._11") (pintype "passive"))
      (node (ref "K3") (pin "6") (pinfunction "N.C._6") (pintype "passive"))
    )
    (net (code "46") (name "Net-(K4-N.C.-Pad11)") (class "Default")
      (node (ref "K4") (pin "11") (pinfunction "N.C._11") (pintype "passive"))
      (node (ref "K4") (pin "6") (pinfunction "N.C._6") (pintype "passive"))
    )
    (net (code "47") (name "Net-(L1-Pad1)") (class "Default")
      (node (ref "L1") (pin "1") (pinfunction "1_1") (pintype "passive"))
      (node (ref "P1") (pin "13") (pinfunction "13_13") (pintype "passive"))
      (node (ref "P1") (pin "14") (pinfunction "14_14") (pintype "passive"))
    )
    (net (code "48") (name "Net-(LS1-COMMON)") (class "Default")
      (node (ref "LS1") (pin "1") (pinfunction "COMMON_1") (pintype "passive"))
      (node (ref "P2") (pin "3") (pinfunction "3_3") (pintype "passive"))
    )
    (net (code "49") (name "Net-(LS1-NO)") (class "Default")
      (node (ref "LS1") (pin "3") (pinfunction "NO_3") (pintype "passive"))
      (node (ref "LS2") (pin "3") (pinfunction "NO_3") (pintype "passive"))
      (node (ref "P4") (pin "3") (pinfunction "3_3") (pintype "passive"))
    )
    (net (code "50") (name "Net-(LS2-COMMON)") (class "Default")
      (node (ref "LS2") (pin "1") (pinfunction "COMMON_1") (pintype "passive"))
      (node (ref "P3") (pin "3") (pinfunction "3_3") (pintype "passive"))
    )
    (net (code "51") (name "Net-(P2-Pad1)") (class "Default")
      (node (ref "P2") (pin "1") (pinfunction "1_1") (pintype "passive"))
      (node (ref "P3") (pin "1") (pinfunction "1_1") (pintype "passive"))
      (node (ref "P4") (pin "1") (pinfunction "1_1") (pintype "passive"))
    )
    (net (code "52") (name "Net-(P5-Pad1)") (class "Default")
      (node (ref "P5") (pin "1") (pinfunction "1_1") (pintype "passive"))
      (node (ref "R32") (pin "2") (pinfunction "2_2") (pintype "passive"))
    )
    (net (code "53") (name "Net-(P5-Pad3)") (class "Default")
      (node (ref "P5") (pin "3") (pinfunction "3_3") (pintype "passive"))
      (node (ref "R16") (pin "2") (pinfunction "2_2") (pintype "passive"))
    )
    (net (code "54") (name "Net-(P8-Pad1)") (class "Default")
      (node (ref "P8") (pin "1") (pinfunction "1_1") (pintype "passive"))
      (node (ref "P8") (pin "2") (pinfunction "2_2") (pintype "passive"))
      (node (ref "P8") (pin "3") (pinfunction "3_3") (pintype "passive"))
      (node (ref "P8") (pin "4") (pinfunction "4_4") (pintype "passive"))
      (node (ref "P8") (pin "5") (pinfunction "5_5") (pintype "passive"))
      (node (ref "P8") (pin "6") (pinfunction "6_6") (pintype "passive"))
      (node (ref "P8") (pin "7") (pinfunction "7_7") (pintype "passive"))
      (node (ref "P8") (pin "8") (pinfunction "8_8") (pintype "passive"))
      (node (ref "P8") (pin "9") (pinfunction "9_9") (pintype "passive"))
    )
    (net (code "55") (name "Net-(P9-Pad1)") (class "Default")
      (node (ref "P9") (pin "1") (pinfunction "1_1") (pintype "passive"))
      (node (ref "P9") (pin "2") (pinfunction "2_2") (pintype "passive"))
      (node (ref "P9") (pin "3") (pinfunction "3_3") (pintype "passive"))
      (node (ref "P9") (pin "4") (pinfunction "4_4") (pintype "passive"))
      (node (ref "P9") (pin "5") (pinfunction "5_5") (pintype "passive"))
      (node (ref "P9") (pin "6") (pinfunction "6_6") (pintype "passive"))
      (node (ref "P9") (pin "7") (pinfunction "7_7") (pintype "passive"))
      (node (ref "P9") (pin "8") (pinfunction "8_8") (pintype "passive"))
      (node (ref "P9") (pin "9") (pinfunction "9_9") (pintype "passive"))
    )
    (net (code "56") (name "Net-(P10-Pad1)") (class "Default")
      (node (ref "P10") (pin "1") (pinfunction "1_1") (pintype "passive"))
      (node (ref "P10") (pin "2") (pinfunction "2_2") (pintype "passive"))
      (node (ref "P10") (pin "3") (pinfunction "3_3") (pintype "passive"))
      (node (ref "P10") (pin "4") (pinfunction "4_4") (pintype "passive"))
      (node (ref "P10") (pin "5") (pinfunction "5_5") (pintype "passive"))
      (node (ref "P10") (pin "6") (pinfunction "6_6") (pintype "passive"))
      (node (ref "P10") (pin "7") (pinfunction "7_7") (pintype "passive"))
      (node (ref "P10") (pin "8") (pinfunction "8_8") (pintype "passive"))
      (node (ref "P10") (pin "9") (pinfunction "9_9") (pintype "passive"))
    )
    (net (code "57") (name "Net-(P11-Pad1)") (class "Default")
      (node (ref "P11") (pin "1") (pinfunction "1_1") (pintype "passive"))
      (node (ref "P11") (pin "2") (pinfunction "2_2") (pintype "passive"))
      (node (ref "P11") (pin "3") (pinfunction "3_3") (pintype "passive"))
      (node (ref "P11") (pin "4") (pinfunction "4_4") (pintype "passive"))
      (node (ref "P11") (pin "5") (pinfunction "5_5") (pintype "passive"))
      (node (ref "P11") (pin "6") (pinfunction "6_6") (pintype "passive"))
      (node (ref "P11") (pin "7") (pinfunction "7_7") (pintype "passive"))
      (node (ref "P11") (pin "8") (pinfunction "8_8") (pintype "passive"))
      (node (ref "P11") (pin "9") (pinfunction "9_9") (pintype "passive"))
    )
    (net (code "58") (name "Net-(U1A-A)") (class "Default")
      (node (ref "R11") (pin "1") (pinfunction "1_1") (pintype "passive"))
      (node (ref "U1") (pin "1") (pinfunction "A_1") (pintype "passive"))
    )
    (net (code "59") (name "Net-(U1A-E)") (class "Default")
      (node (ref "R7") (pin "1") (pinfunction "1_1") (pintype "passive"))
      (node (ref "U1") (pin "15") (pinfunction "E_15") (pintype "passive"))
    )
    (net (code "60") (name "Net-(U1B-A)") (class "Default")
      (node (ref "R5") (pin "1") (pinfunction "1_1") (pintype "passive"))
      (node (ref "U1") (pin "3") (pinfunction "A_3") (pintype "passive"))
    )
    (net (code "61") (name "Net-(U1B-E)") (class "Default")
      (node (ref "R6") (pin "1") (pinfunction "1_1") (pintype "passive"))
      (node (ref "U1") (pin "13") (pinfunction "E_13") (pintype "passive"))
    )
    (net (code "62") (name "Net-(U1C-A)") (class "Default")
      (node (ref "R2") (pin "1") (pinfunction "1_1") (pintype "passive"))
      (node (ref "U1") (pin "5") (pinfunction "A_5") (pintype "passive"))
    )
    (net (code "63") (name "Net-(U1C-E)") (class "Default")
      (node (ref "R4") (pin "1") (pinfunction "1_1") (pintype "passive"))
      (node (ref "U1") (pin "11") (pinfunction "E_11") (pintype "passive"))
    )
    (net (code "64") (name "Net-(U1D-A)") (class "Default")
      (node (ref "R1") (pin "1") (pinfunction "1_1") (pintype "passive"))
      (node (ref "U1") (pin "7") (pinfunction "A_7") (pintype "passive"))
    )
    (net (code "65") (name "Net-(U1D-E)") (class "Default")
      (node (ref "R3") (pin "1") (pinfunction "1_1") (pintype "passive"))
      (node (ref "U1") (pin "9") (pinfunction "E_9") (pintype "passive"))
    )
    (net (code "66") (name "Net-(U3-IN_1)") (class "Default")
      (node (ref "R10") (pin "2") (pinfunction "2_2") (pintype "passive"))
      (node (ref "U3") (pin "1") (pinfunction "IN_1_1") (pintype "input"))
    )
    (net (code "67") (name "Net-(U3-IN_2)") (class "Default")
      (node (ref "R9") (pin "2") (pinfunction "2_2") (pintype "passive"))
      (node (ref "U3") (pin "2") (pinfunction "IN_2_2") (pintype "input"))
    )
    (net (code "68") (name "Net-(U3-IN_3)") (class "Default")
      (node (ref "R8") (pin "2") (pinfunction "2_2") (pintype "passive"))
      (node (ref "U3") (pin "3") (pinfunction "IN_3_3") (pintype "input"))
    )
    (net (code "69") (name "Net-(U3-IN_4)") (class "Default")
      (node (ref "R7") (pin "2") (pinfunction "2_2") (pintype "passive"))
      (node (ref "U3") (pin "4") (pinfunction "IN_4_4") (pintype "input"))
    )
    (net (code "70") (name "Net-(U3-IN_5)") (class "Default")
      (node (ref "R6") (pin "2") (pinfunction "2_2") (pintype "passive"))
      (node (ref "U3") (pin "5") (pinfunction "IN_5_5") (pintype "input"))
    )
    (net (code "71") (name "Net-(U3-IN_6)") (class "Default")
      (node (ref "R4") (pin "2") (pinfunction "2_2") (pintype "passive"))
      (node (ref "U3") (pin "6") (pinfunction "IN_6_6") (pintype "input"))
    )
    (net (code "72") (name "Net-(U3-IN_7)") (class "Default")
      (node (ref "R3") (pin "2") (pinfunction "2_2") (pintype "passive"))
      (node (ref "U3") (pin "7") (pinfunction "IN_7_7") (pintype "input"))
    )
    (net (code "73") (name "Net-(U4A-A)") (class "Default")
      (node (ref "R17") (pin "1") (pinfunction "1_1") (pintype "passive"))
      (node (ref "U4") (pin "1") (pinfunction "A_1") (pintype "passive"))
    )
    (net (code "74") (name "Net-(U4B-A)") (class "Default")
      (node (ref "R15") (pin "1") (pinfunction "1_1") (pintype "passive"))
      (node (ref "U4") (pin "3") (pinfunction "A_3") (pintype "passive"))
    )
    (net (code "75") (name "Net-(U4B-E)") (class "Default")
      (node (ref "R10") (pin "1") (pinfunction "1_1") (pintype "passive"))
      (node (ref "U4") (pin "13") (pinfunction "E_13") (pintype "passive"))
    )
    (net (code "76") (name "Net-(U4C-A)") (class "Default")
      (node (ref "R14") (pin "1") (pinfunction "1_1") (pintype "passive"))
      (node (ref "U4") (pin "5") (pinfunction "A_5") (pintype "passive"))
    )
    (net (code "77") (name "Net-(U4C-E)") (class "Default")
      (node (ref "R9") (pin "1") (pinfunction "1_1") (pintype "passive"))
      (node (ref "U4") (pin "11") (pinfunction "E_11") (pintype "passive"))
    )
    (net (code "78") (name "Net-(U4D-A)") (class "Default")
      (node (ref "R13") (pin "1") (pinfunction "1_1") (pintype "passive"))
      (node (ref "U4") (pin "7") (pinfunction "A_7") (pintype "passive"))
    )
    (net (code "79") (name "Net-(U4D-E)") (class "Default")
      (node (ref "R8") (pin "1") (pinfunction "1_1") (pintype "passive"))
      (node (ref "U4") (pin "9") (pinfunction "E_9") (pintype "passive"))
    )
    (net (code "80") (name "Net-(U5A-A)") (class "Default")
      (node (ref "R33") (pin "1") (pinfunction "1_1") (pintype "passive"))
      (node (ref "U5") (pin "1") (pinfunction "A_1") (pintype "passive"))
    )
    (net (code "81") (name "Net-(U5A-E)") (class "Default")
      (node (ref "R26") (pin "1") (pinfunction "1_1") (pintype "passive"))
      (node (ref "U5") (pin "15") (pinfunction "E_15") (pintype "passive"))
    )
    (net (code "82") (name "Net-(U5B-A)") (class "Default")
      (node (ref "R31") (pin "1") (pinfunction "1_1") (pintype "passive"))
      (node (ref "U5") (pin "3") (pinfunction "A_3") (pintype "passive"))
    )
    (net (code "83") (name "Net-(U5B-E)") (class "Default")
      (node (ref "R25") (pin "1") (pinfunction "1_1") (pintype "passive"))
      (node (ref "U5") (pin "13") (pinfunction "E_13") (pintype "passive"))
    )
    (net (code "84") (name "Net-(U5C-A)") (class "Default")
      (node (ref "R24") (pin "1") (pinfunction "1_1") (pintype "passive"))
      (node (ref "U5") (pin "5") (pinfunction "A_5") (pintype "passive"))
    )
    (net (code "85") (name "Net-(U5C-E)") (class "Default")
      (node (ref "R23") (pin "1") (pinfunction "1_1") (pintype "passive"))
      (node (ref "U5") (pin "11") (pinfunction "E_11") (pintype "passive"))
    )
    (net (code "86") (name "Net-(U5D-A)") (class "Default")
      (node (ref "R21") (pin "1") (pinfunction "1_1") (pintype "passive"))
      (node (ref "U5") (pin "7") (pinfunction "A_7") (pintype "passive"))
    )
    (net (code "87") (name "Net-(U5D-E)") (class "Default")
      (node (ref "R22") (pin "1") (pinfunction "1_1") (pintype "passive"))
      (node (ref "U5") (pin "9") (pinfunction "E_9") (pintype "passive"))
    )
    (net (code "88") (name "Net-(U7-EN1)") (class "Default")
      (node (ref "R101") (pin "2") (pinfunction "2_2") (pintype "passive"))
      (node (ref "R20") (pin "1") (pinfunction "1_1") (pintype "passive"))
      (node (ref "U7") (pin "1") (pinfunction "EN1_1") (pintype "input"))
      (node (ref "U7") (pin "9") (pinfunction "EN2_9") (pintype "input"))
    )
    (net (code "89") (name "Net-(U7-IN1)") (class "Default")
      (node (ref "R22") (pin "2") (pinfunction "2_2") (pintype "passive"))
      (node (ref "R30") (pin "2") (pinfunction "2_2") (pintype "passive"))
      (node (ref "U7") (pin "2") (pinfunction "IN1_2") (pintype "input"))
    )
    (net (code "90") (name "Net-(U7-IN2)") (class "Default")
      (node (ref "R23") (pin "2") (pinfunction "2_2") (pintype "passive"))
      (node (ref "R29") (pin "2") (pinfunction "2_2") (pintype "passive"))
      (node (ref "U7") (pin "7") (pinfunction "IN2_7") (pintype "input"))
    )
    (net (code "91") (name "Net-(U7-IN3)") (class "Default")
      (node (ref "R25") (pin "2") (pinfunction "2_2") (pintype "passive"))
      (node (ref "R28") (pin "2") (pinfunction "2_2") (pintype "passive"))
      (node (ref "U7") (pin "10") (pinfunction "IN3_10") (pintype "input"))
    )
    (net (code "92") (name "Net-(U7-IN4)") (class "Default")
      (node (ref "R26") (pin "2") (pinfunction "2_2") (pintype "passive"))
      (node (ref "R27") (pin "2") (pinfunction "2_2") (pintype "passive"))
      (node (ref "U7") (pin "15") (pinfunction "IN4_15") (pintype "input"))
    )
    (net (code "93") (name "Net-(U8A-A)") (class "Default")
      (node (ref "R46") (pin "1") (pinfunction "1_1") (pintype "passive"))
      (node (ref "U8") (pin "1") (pinfunction "A_1") (pintype "passive"))
    )
    (net (code "94") (name "Net-(U8A-E)") (class "Default")
      (node (ref "R39") (pin "1") (pinfunction "1_1") (pintype "passive"))
      (node (ref "U8") (pin "15") (pinfunction "E_15") (pintype "passive"))
    )
    (net (code "95") (name "Net-(U8B-A)") (class "Default")
      (node (ref "R45") (pin "1") (pinfunction "1_1") (pintype "passive"))
      (node (ref "U8") (pin "3") (pinfunction "A_3") (pintype "passive"))
    )
    (net (code "96") (name "Net-(U8B-E)") (class "Default")
      (node (ref "R38") (pin "1") (pinfunction "1_1") (pintype "passive"))
      (node (ref "U8") (pin "13") (pinfunction "E_13") (pintype "passive"))
    )
    (net (code "97") (name "Net-(U8C-A)") (class "Default")
      (node (ref "R37") (pin "1") (pinfunction "1_1") (pintype "passive"))
      (node (ref "U8") (pin "5") (pinfunction "A_5") (pintype "passive"))
    )
    (net (code "98") (name "Net-(U8C-E)") (class "Default")
      (node (ref "R36") (pin "1") (pinfunction "1_1") (pintype "passive"))
      (node (ref "U8") (pin "11") (pinfunction "E_11") (pintype "passive"))
    )
    (net (code "99") (name "Net-(U8D-A)") (class "Default")
      (node (ref "R34") (pin "1") (pinfunction "1_1") (pintype "passive"))
      (node (ref "U8") (pin "7") (pinfunction "A_7") (pintype "passive"))
    )
    (net (code "100") (name "Net-(U8D-E)") (class "Default")
      (node (ref "R35") (pin "1") (pinfunction "1_1") (pintype "passive"))
      (node (ref "U8") (pin "9") (pinfunction "E_9") (pintype "passive"))
    )
    (net (code "101") (name "Net-(U9-EN1)") (class "Default")
      (node (ref "R102") (pin "2") (pinfunction "2_2") (pintype "passive"))
      (node (ref "R44") (pin "2") (pinfunction "2_2") (pintype "passive"))
      (node (ref "U9") (pin "1") (pinfunction "EN1_1") (pintype "input"))
      (node (ref "U9") (pin "9") (pinfunction "EN2_9") (pintype "input"))
    )
    (net (code "102") (name "Net-(U9-IN1)") (class "Default")
      (node (ref "R35") (pin "2") (pinfunction "2_2") (pintype "passive"))
      (node (ref "R43") (pin "2") (pinfunction "2_2") (pintype "passive"))
      (node (ref "U9") (pin "2") (pinfunction "IN1_2") (pintype "input"))
    )
    (net (code "103") (name "Net-(U9-IN2)") (class "Default")
      (node (ref "R36") (pin "2") (pinfunction "2_2") (pintype "passive"))
      (node (ref "R42") (pin "2") (pinfunction "2_2") (pintype "passive"))
      (node (ref "U9") (pin "7") (pinfunction "IN2_7") (pintype "input"))
    )
    (net (code "104") (name "Net-(U9-IN3)") (class "Default")
      (node (ref "R38") (pin "2") (pinfunction "2_2") (pintype "passive"))
      (node (ref "R41") (pin "2") (pinfunction "2_2") (pintype "passive"))
      (node (ref "U9") (pin "10") (pinfunction "IN3_10") (pintype "input"))
    )
    (net (code "105") (name "Net-(U9-IN4)") (class "Default")
      (node (ref "R39") (pin "2") (pinfunction "2_2") (pintype "passive"))
      (node (ref "R40") (pin "2") (pinfunction "2_2") (pintype "passive"))
      (node (ref "U9") (pin "15") (pinfunction "IN4_15") (pintype "input"))
    )
    (net (code "106") (name "Net-(U10-FB)") (class "Default")
      (node (ref "C5") (pin "2") (pinfunction "2_2") (pintype "passive"))
      (node (ref "R12") (pin "1") (pinfunction "1_1") (pintype "passive"))
      (node (ref "R16") (pin "1") (pinfunction "1_1") (pintype "passive"))
      (node (ref "R18") (pin "1") (pinfunction "1_1") (pintype "passive"))
      (node (ref "R32") (pin "1") (pinfunction "1_1") (pintype "passive"))
      (node (ref "U10") (pin "4") (pinfunction "FB_4") (pintype "passive"))
    )
    (net (code "107") (name "Net-(U10-Vout)") (class "Default")
      (node (ref "D4") (pin "2") (pinfunction "2_2") (pintype "passive"))
      (node (ref "L32") (pin "1") (pinfunction "1_1") (pintype "passive"))
      (node (ref "U10") (pin "2") (pinfunction "Vout_2") (pintype "passive"))
    )
    (net (code "108") (name "VCC_24V") (class "Default")
      (node (ref "C2") (pin "2") (pinfunction "2_2") (pintype "passive"))
      (node (ref "C6") (pin "1") (pinfunction "1_1") (pintype "passive"))
      (node (ref "D1") (pin "2") (pinfunction "K_2") (pintype "passive"))
      (node (ref "D14") (pin "2") (pinfunction "K_2") (pintype "passive"))
      (node (ref "D2") (pin "2") (pinfunction "K_2") (pintype "passive"))
      (node (ref "D20") (pin "2") (pinfunction "K_2") (pintype "passive"))
      (node (ref "D6") (pin "2") (pinfunction "K_2") (pintype "passive"))
      (node (ref "D8") (pin "2") (pinfunction "K_2") (pintype "passive"))
      (node (ref "F3") (pin "1") (pinfunction "1_1") (pintype "passive"))
      (node (ref "K1") (pin "1") (pinfunction "+_1") (pintype "passive"))
      (node (ref "K2") (pin "1") (pinfunction "+_1") (pintype "passive"))
      (node (ref "K3") (pin "1") (pinfunction "+_1") (pintype "passive"))
      (node (ref "K4") (pin "1") (pinfunction "+_1") (pintype "passive"))
      (node (ref "LS1") (pin "4") (pinfunction "COIL1_4") (pintype "passive"))
      (node (ref "LS2") (pin "4") (pinfunction "COIL1_4") (pintype "passive"))
      (node (ref "P102") (pin "2") (pinfunction "2_2") (pintype "passive"))
      (node (ref "R102") (pin "1") (pinfunction "1_1") (pintype "passive"))
      (node (ref "R20") (pin "2") (pinfunction "2_2") (pintype "passive"))
      (node (ref "U1") (pin "10") (pinfunction "C_10") (pintype "passive"))
      (node (ref "U1") (pin "12") (pinfunction "C_12") (pintype "passive"))
      (node (ref "U1") (pin "14") (pinfunction "C_14") (pintype "passive"))
      (node (ref "U1") (pin "16") (pinfunction "C_16") (pintype "passive"))
      (node (ref "U10") (pin "1") (pinfunction "Vin_1") (pintype "passive"))
      (node (ref "U3") (pin "9") (pinfunction "CLAMP_9") (pintype "passive"))
      (node (ref "U4") (pin "10") (pinfunction "C_10") (pintype "passive"))
      (node (ref "U4") (pin "12") (pinfunction "C_12") (pintype "passive"))
      (node (ref "U4") (pin "14") (pinfunction "C_14") (pintype "passive"))
      (node (ref "U4") (pin "16") (pinfunction "C_16") (pintype "passive"))
      (node (ref "U5") (pin "10") (pinfunction "C_10") (pintype "passive"))
      (node (ref "U5") (pin "12") (pinfunction "C_12") (pintype "passive"))
      (node (ref "U5") (pin "14") (pinfunction "C_14") (pintype "passive"))
      (node (ref "U5") (pin "16") (pinfunction "C_16") (pintype "passive"))
      (node (ref "U8") (pin "10") (pinfunction "C_10") (pintype "passive"))
      (node (ref "U8") (pin "12") (pinfunction "C_12") (pintype "passive"))
      (node (ref "U8") (pin "14") (pinfunction "C_14") (pintype "passive"))
      (node (ref "U8") (pin "16") (pinfunction "C_16") (pintype "passive"))
    )
    (net (code "109") (name "unconnected-(LS1-NC-Pad2)") (class "Default")
      (node (ref "LS1") (pin "2") (pinfunction "NC_2") (pintype "passive"))
    )
    (net (code "110") (name "unconnected-(LS2-NC-Pad2)") (class "Default")
      (node (ref "LS2") (pin "2") (pinfunction "NC_2") (pintype "passive"))
    )
    (net (code "111") (name "unconnected-(P2-Pad2)") (class "Default")
      (node (ref "P2") (pin "2") (pinfunction "2_2") (pintype "passive"))
    )
    (net (code "112") (name "unconnected-(P3-Pad2)") (class "Default")
      (node (ref "P3") (pin "2") (pinfunction "2_2") (pintype "passive"))
    )
    (net (code "113") (name "unconnected-(P4-Pad2)") (class "Default")
      (node (ref "P4") (pin "2") (pinfunction "2_2") (pintype "passive"))
    )
    (net (code "114") (name "unconnected-(U3-OUT_1-Pad16)") (class "Default")
      (node (ref "U3") (pin "16") (pinfunction "OUT_1_16") (pintype "output"))
    )
    (net (code "115") (name "unconnected-(U4A-E-Pad15)") (class "Default")
      (node (ref "U4") (pin "15") (pinfunction "E_15") (pintype "passive"))
    )
  )
)
